# GPS_POWER.net
KiCad netlist of a schematic drawn in Altium Designer
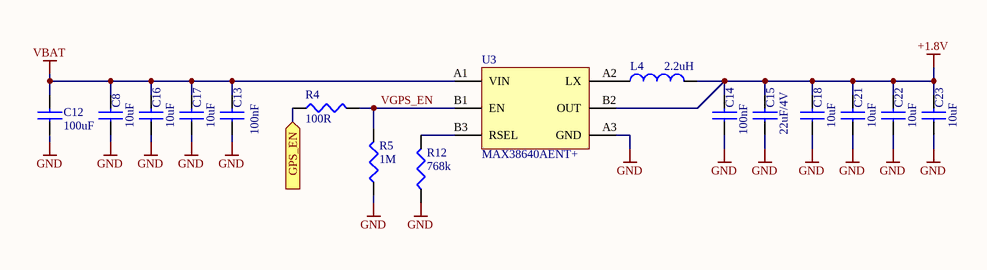
[diagram p0: GPS_POWER.SchDoc]

(export (version "E")
  (design (tool "Eeschema 10.0.6"))
  (components
    (comp (ref "C8")
      (value "10uF")
      (footprint "CAP0603")
      (description "Cap Ceramic 10uF 10V X5R 10% SMD 0603 85C Paper T/R")
      (fields
        (field (name "MANUFACTURER") "Samsung")
        (field (name "MANUFACTURER PART NUMBER") "CL10A106KP8NNNC")
      )
      (libsource (lib "Passive") (part "C - 10uF/10V"))
    )
    (comp (ref "C12")
      (value "100uF")
      (footprint "CAP0805")
      (description "Multilayer Ceramic Capacitors MLCC - SMD/SMT 0805 100uF 4volts *Derate Voltage/Temp")
      (fields
        (field (name "MANUFACTURER") "Murata")
        (field (name "MANUFACTURER PART NUMBER") "GRM21BR60G107ME15L")
      )
      (libsource (lib "Passive") (part "C - 100uF/0805"))
    )
    (comp (ref "C13")
      (value "100nF")
      (footprint "CAP0402")
      (fields
        (field (name "MANUFACTURER") "Multicomp")
        (field (name "MANUFACTURER PART NUMBER") "MC0402X104J160CT")
        (field (name "TOLERANCE") "5%")
      )
      (libsource (lib "Passive") (part "C - 100nF/0402"))
    )
    (comp (ref "C14")
      (value "100nF")
      (footprint "CAP0402")
      (fields
        (field (name "MANUFACTURER") "Multicomp")
        (field (name "MANUFACTURER PART NUMBER") "MC0402X104J160CT")
        (field (name "TOLERANCE") "5%")
      )
      (libsource (lib "Passive") (part "C - 100nF/0402"))
    )
    (comp (ref "C15")
      (value "22uF/4V")
      (footprint "CAP0603")
      (description "SMD Multilayer Ceramic Capacitor, 22 µF, 4 V, 0603 [1608 Metric], ± 20%, X5R, GRM Series")
      (fields
        (field (name "MANUFACTURER") "Samsung")
        (field (name "MANUFACTURER PART NUMBER") "GRM188R60G226MEA0D")
      )
      (libsource (lib "Passive") (part "C - 10uF/10V"))
    )
    (comp (ref "C16")
      (value "10uF")
      (footprint "CAP0603")
      (description "Cap Ceramic 10uF 10V X5R 10% SMD 0603 85C Paper T/R")
      (fields
        (field (name "MANUFACTURER") "Samsung")
        (field (name "MANUFACTURER PART NUMBER") "CL10A106KP8NNNC")
      )
      (libsource (lib "Passive") (part "C - 10uF/10V"))
    )
    (comp (ref "C17")
      (value "10uF")
      (footprint "CAP0603")
      (description "Cap Ceramic 10uF 10V X5R 10% SMD 0603 85C Paper T/R")
      (fields
        (field (name "MANUFACTURER") "Samsung")
        (field (name "MANUFACTURER PART NUMBER") "CL10A106KP8NNNC")
      )
      (libsource (lib "Passive") (part "C - 10uF/10V"))
    )
    (comp (ref "C18")
      (value "10uF")
      (footprint "CAP0603")
      (description "Cap Ceramic 10uF 10V X5R 10% SMD 0603 85C Paper T/R")
      (fields
        (field (name "MANUFACTURER") "Samsung")
        (field (name "MANUFACTURER PART NUMBER") "CL10A106KP8NNNC")
      )
      (libsource (lib "Passive") (part "C - 10uF/10V"))
    )
    (comp (ref "C21")
      (value "10uF")
      (footprint "CAP0603")
      (description "Cap Ceramic 10uF 10V X5R 10% SMD 0603 85C Paper T/R")
      (fields
        (field (name "MANUFACTURER") "Samsung")
        (field (name "MANUFACTURER PART NUMBER") "CL10A106KP8NNNC")
      )
      (libsource (lib "Passive") (part "C - 10uF/10V"))
    )
    (comp (ref "C22")
      (value "10uF")
      (footprint "CAP0603")
      (description "Cap Ceramic 10uF 10V X5R 10% SMD 0603 85C Paper T/R")
      (fields
        (field (name "MANUFACTURER") "Samsung")
        (field (name "MANUFACTURER PART NUMBER") "CL10A106KP8NNNC")
      )
      (libsource (lib "Passive") (part "C - 10uF/10V"))
    )
    (comp (ref "C23")
      (value "10uF")
      (footprint "CAP0603")
      (description "Cap Ceramic 10uF 10V X5R 10% SMD 0603 85C Paper T/R")
      (fields
        (field (name "MANUFACTURER") "Samsung")
        (field (name "MANUFACTURER PART NUMBER") "CL10A106KP8NNNC")
      )
      (libsource (lib "Passive") (part "C - 10uF/10V"))
    )
    (comp (ref "L4")
      (value "2.2uH")
      (footprint "IND2.3X1.7")
      (fields
        (field (name "MANUFACTURER") "Bourns")
        (field (name "MANUFACTURER PART NUMBER") "SRN2009T-2R2M")
        (field (name "IRNAS PART NO.") "/")
      )
      (libsource (lib "Passive") (part "L - 2.2 uH 900mA"))
    )
    (comp (ref "R4")
      (value "100R")
      (footprint "RES0402")
      (fields
        (field (name "MANUFACTURER") "Multicomp")
        (field (name "MANUFACTURER PART NUMBER") "MCMR04X1000FTL")
        (field (name "TOLERANCE") "1%")
      )
      (libsource (lib "Passive") (part "R - 100R/0402"))
    )
    (comp (ref "R5")
      (value "1M")
      (footprint "RES0402")
      (description "MCMR04X1004FTL RES, 1M, 1%, 0.0625W, 0402, THICK FILM")
      (fields
        (field (name "MANUFACTURER") "MULTICOMP")
        (field (name "MANUFACTURER PART NUMBER") "MC0063W060311M")
      )
      (libsource (lib "Passive") (part "R - 1M/0402"))
    )
    (comp (ref "R12")
      (value "768k")
      (footprint "RES0603")
      (description "SMD Chip Resistor, 0402 [1005 Metric], 768 kohm, WR04 Series, 50 V, Thick Film, 62.5 mW")
      (fields (field (name "MANUFACTURER") "Vishay") (field (name "TOLERANCE") "1%"))
      (libsource (lib "Passive") (part "R - 768k/0402"))
    )
    (comp (ref "U3")
      (value "MAX38640AENT+")
      (footprint "WLP-6")
      (description "Switching Voltage Regulators Tiny 300nA nanoPower Buck converters in uDFN and WLP pacakges")
      (fields (field (name "MANUFACTURER") "ROHM") (field (name "MANUFACTURER PART NUMBER") "BD70522GUL"))
      (libsource (lib "Active") (part "V_SW - MAX38640AENT+"))
    )
  )
  (nets
    (net (code "1") (name "+1.8V") (class "Default")
      (node (ref "C14") (pin "2") (pinfunction "2_2") (pintype "passive"))
      (node (ref "C15") (pin "2") (pinfunction "2_2") (pintype "passive"))
      (node (ref "C18") (pin "2") (pinfunction "2_2") (pintype "passive"))
      (node (ref "C21") (pin "2") (pinfunction "2_2") (pintype "passive"))
      (node (ref "C22") (pin "2") (pinfunction "2_2") (pintype "passive"))
      (node (ref "C23") (pin "2") (pinfunction "2_2") (pintype "passive"))
      (node (ref "L4") (pin "2") (pinfunction "2_2") (pintype "passive"))
      (node (ref "U3") (pin "B2") (pinfunction "OUT_B2") (pintype "passive"))
    )
    (net (code "2") (name "/GPS_EN") (class "Default")
      (node (ref "R4") (pin "1") (pinfunction "1_1") (pintype "passive"))
    )
    (net (code "3") (name "/VGPS_EN") (class "Default")
      (node (ref "R4") (pin "2") (pinfunction "2_2") (pintype "passive"))
      (node (ref "R5") (pin "2") (pinfunction "2_2") (pintype "passive"))
      (node (ref "U3") (pin "B1") (pinfunction "EN_B1") (pintype "passive"))
    )
    (net (code "4") (name "GND") (class "Default")
      (node (ref "C12") (pin "1") (pinfunction "1_1") (pintype "passive"))
      (node (ref "C13") (pin "1") (pinfunction "1_1") (pintype "passive"))
      (node (ref "C14") (pin "1") (pinfunction "1_1") (pintype "passive"))
      (node (ref "C15") (pin "1") (pinfunction "1_1") (pintype "passive"))
      (node (ref "C16") (pin "1") (pinfunction "1_1") (pintype "passive"))
      (node (ref "C17") (pin "1") (pinfunction "1_1") (pintype "passive"))
      (node (ref "C18") (pin "1") (pinfunction "1_1") (pintype "passive"))
      (node (ref "C21") (pin "1") (pinfunction "1_1") (pintype "passive"))
      (node (ref "C22") (pin "1") (pinfunction "1_1") (pintype "passive"))
      (node (ref "C23") (pin "1") (pinfunction "1_1") (pintype "passive"))
      (node (ref "C8") (pin "1") (pinfunction "1_1") (pintype "passive"))
      (node (ref "R12") (pin "1") (pinfunction "1_1") (pintype "passive"))
      (node (ref "R5") (pin "1") (pinfunction "1_1") (pintype "passive"))
      (node (ref "U3") (pin "A3") (pinfunction "GND_A3") (pintype "passive"))
    )
    (net (code "5") (name "Net-(U3-LX)") (class "Default")
      (node (ref "L4") (pin "1") (pinfunction "1_1") (pintype "passive"))
      (node (ref "U3") (pin "A2") (pinfunction "LX_A2") (pintype "passive"))
    )
    (net (code "6") (name "Net-(U3-RSEL)") (class "Default")
      (node (ref "R12") (pin "2") (pinfunction "2_2") (pintype "passive"))
      (node (ref "U3") (pin "B3") (pinfunction "RSEL_B3") (pintype "passive"))
    )
    (net (code "7") (name "VBAT") (class "Default")
      (node (ref "C12") (pin "2") (pinfunction "2_2") (pintype "passive"))
      (node (ref "C13") (pin "2") (pinfunction "2_2") (pintype "passive"))
      (node (ref "C16") (pin "2") (pinfunction "2_2") (pintype "passive"))
      (node (ref "C17") (pin "2") (pinfunction "2_2") (pintype "passive"))
      (node (ref "C8") (pin "2") (pinfunction "2_2") (pintype "passive"))
      (node (ref "U3") (pin "A1") (pinfunction "VIN_A1") (pintype "passive"))
    )
  )
)
